# Power_Distribution_24v.net
KiCad netlist of a schematic drawn in EAGLE
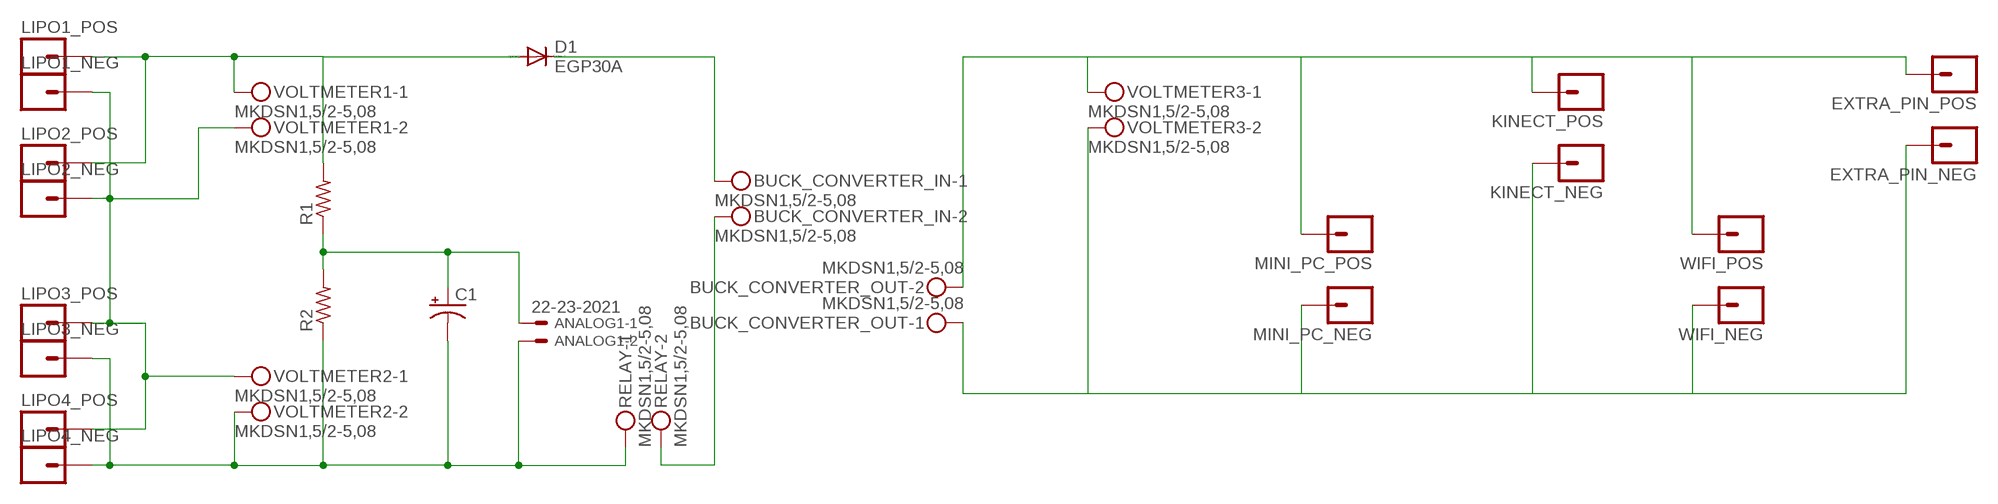
[diagram p0: schematic, sheet 1]

(export (version "E")
  (design (tool "Eeschema 10.0.6"))
  (components
    (comp (ref "ANALOG1")
      (value "22-23-2021")
      (footprint "eagle-import:22-23-2021")
      (fields (field (name "MF") "MOLEX"))
      (libsource (lib "eagle-import") (part "22-23-2021"))
    )
    (comp (ref "BUCK_CONVERTER_IN")
      (value "MKDSN1,5/2-5,08")
      (footprint "eagle-import:MKDSN1,5_2-5,08")
      (libsource (lib "eagle-import") (part "MKDSN1,5/2-5,08"))
    )
    (comp (ref "BUCK_CONVERTER_OUT")
      (value "MKDSN1,5/2-5,08")
      (footprint "eagle-import:MKDSN1,5_2-5,08")
      (libsource (lib "eagle-import") (part "MKDSN1,5/2-5,08"))
    )
    (comp (ref "C1")
      (value "CPOL-USE2-5")
      (footprint "eagle-import:E2-5")
      (libsource (lib "eagle-import") (part "CPOL-USE2-5"))
    )
    (comp (ref "D1")
      (value "EGP30A")
      (footprint "eagle-import:DO201-15")
      (libsource (lib "eagle-import") (part "EGP30A"))
    )
    (comp (ref "EXTRA_PIN_NEG")
      (value "M01PTH_2MM")
      (footprint "eagle-import:1X01_2MM")
      (libsource (lib "eagle-import") (part "M01PTH_2MM"))
    )
    (comp (ref "EXTRA_PIN_POS")
      (value "M01PTH_2MM")
      (footprint "eagle-import:1X01_2MM")
      (libsource (lib "eagle-import") (part "M01PTH_2MM"))
    )
    (comp (ref "KINECT_NEG")
      (value "M01PTH_2MM")
      (footprint "eagle-import:1X01_2MM")
      (libsource (lib "eagle-import") (part "M01PTH_2MM"))
    )
    (comp (ref "KINECT_POS")
      (value "M01PTH_2MM")
      (footprint "eagle-import:1X01_2MM")
      (libsource (lib "eagle-import") (part "M01PTH_2MM"))
    )
    (comp (ref "LIPO1_NEG")
      (value "M01PTH_2MM")
      (footprint "eagle-import:1X01_2MM")
      (libsource (lib "eagle-import") (part "M01PTH_2MM"))
    )
    (comp (ref "LIPO1_POS")
      (value "M01PTH_2MM")
      (footprint "eagle-import:1X01_2MM")
      (libsource (lib "eagle-import") (part "M01PTH_2MM"))
    )
    (comp (ref "LIPO2_NEG")
      (value "M01PTH_2MM")
      (footprint "eagle-import:1X01_2MM")
      (libsource (lib "eagle-import") (part "M01PTH_2MM"))
    )
    (comp (ref "LIPO2_POS")
      (value "M01PTH_2MM")
      (footprint "eagle-import:1X01_2MM")
      (libsource (lib "eagle-import") (part "M01PTH_2MM"))
    )
    (comp (ref "LIPO3_NEG")
      (value "M01PTH_2MM")
      (footprint "eagle-import:1X01_2MM")
      (libsource (lib "eagle-import") (part "M01PTH_2MM"))
    )
    (comp (ref "LIPO3_POS")
      (value "M01PTH_2MM")
      (footprint "eagle-import:1X01_2MM")
      (libsource (lib "eagle-import") (part "M01PTH_2MM"))
    )
    (comp (ref "LIPO4_NEG")
      (value "M01PTH_2MM")
      (footprint "eagle-import:1X01_2MM")
      (libsource (lib "eagle-import") (part "M01PTH_2MM"))
    )
    (comp (ref "LIPO4_POS")
      (value "M01PTH_2MM")
      (footprint "eagle-import:1X01_2MM")
      (libsource (lib "eagle-import") (part "M01PTH_2MM"))
    )
    (comp (ref "MINI_PC_NEG")
      (value "M01PTH_2MM")
      (footprint "eagle-import:1X01_2MM")
      (libsource (lib "eagle-import") (part "M01PTH_2MM"))
    )
    (comp (ref "MINI_PC_POS")
      (value "M01PTH_2MM")
      (footprint "eagle-import:1X01_2MM")
      (libsource (lib "eagle-import") (part "M01PTH_2MM"))
    )
    (comp (ref "R1")
      (value "R-US_0207/10")
      (footprint "eagle-import:0207_10")
      (libsource (lib "eagle-import") (part "R-US_0207/10"))
    )
    (comp (ref "R2")
      (value "R-US_0207/10")
      (footprint "eagle-import:0207_10")
      (libsource (lib "eagle-import") (part "R-US_0207/10"))
    )
    (comp (ref "RELAY")
      (value "MKDSN1,5/2-5,08")
      (footprint "eagle-import:MKDSN1,5_2-5,08")
      (libsource (lib "eagle-import") (part "MKDSN1,5/2-5,08"))
    )
    (comp (ref "VOLTMETER1")
      (value "MKDSN1,5/2-5,08")
      (footprint "eagle-import:MKDSN1,5_2-5,08")
      (libsource (lib "eagle-import") (part "MKDSN1,5/2-5,08"))
    )
    (comp (ref "VOLTMETER2")
      (value "MKDSN1,5/2-5,08")
      (footprint "eagle-import:MKDSN1,5_2-5,08")
      (libsource (lib "eagle-import") (part "MKDSN1,5/2-5,08"))
    )
    (comp (ref "VOLTMETER3")
      (value "MKDSN1,5/2-5,08")
      (footprint "eagle-import:MKDSN1,5_2-5,08")
      (libsource (lib "eagle-import") (part "MKDSN1,5/2-5,08"))
    )
    (comp (ref "WIFI_NEG")
      (value "M01PTH_2MM")
      (footprint "eagle-import:1X01_2MM")
      (libsource (lib "eagle-import") (part "M01PTH_2MM"))
    )
    (comp (ref "WIFI_POS")
      (value "M01PTH_2MM")
      (footprint "eagle-import:1X01_2MM")
      (libsource (lib "eagle-import") (part "M01PTH_2MM"))
    )
  )
  (nets
    (net (code "1") (name "Net-(ANALOG1A-S)") (class "Default")
      (node (ref "ANALOG1") (pin "1") (pinfunction "S_1") (pintype "passive"))
      (node (ref "C1") (pin "+") (pinfunction "+_+") (pintype "passive"))
      (node (ref "R1") (pin "1") (pinfunction "1_1") (pintype "passive"))
      (node (ref "R2") (pin "2") (pinfunction "2_2") (pintype "passive"))
    )
    (net (code "2") (name "Net-(ANALOG1B-S)") (class "Default")
      (node (ref "ANALOG1") (pin "2") (pinfunction "S_2") (pintype "passive"))
      (node (ref "C1") (pin "-") (pinfunction "-_-") (pintype "passive"))
      (node (ref "LIPO3_NEG") (pin "1") (pinfunction "1_1") (pintype "passive"))
      (node (ref "LIPO4_NEG") (pin "1") (pinfunction "1_1") (pintype "passive"))
      (node (ref "R2") (pin "1") (pinfunction "1_1") (pintype "passive"))
      (node (ref "RELAY") (pin "1") (pinfunction "KL_1") (pintype "passive"))
      (node (ref "VOLTMETER2") (pin "2") (pinfunction "KL_2") (pintype "passive"))
    )
    (net (code "3") (name "Net-(BUCK_CONVERTER_INA-KL)") (class "Default")
      (node (ref "BUCK_CONVERTER_IN") (pin "1") (pinfunction "KL_1") (pintype "passive"))
      (node (ref "D1") (pin "C") (pinfunction "C_C") (pintype "passive"))
    )
    (net (code "4") (name "Net-(BUCK_CONVERTER_INB-KL)") (class "Default")
      (node (ref "BUCK_CONVERTER_IN") (pin "2") (pinfunction "KL_2") (pintype "passive"))
      (node (ref "RELAY") (pin "2") (pinfunction "KL_2") (pintype "passive"))
    )
    (net (code "5") (name "Net-(BUCK_CONVERTER_OUTA-KL)") (class "Default")
      (node (ref "BUCK_CONVERTER_OUT") (pin "1") (pinfunction "KL_1") (pintype "passive"))
      (node (ref "EXTRA_PIN_NEG") (pin "1") (pinfunction "1_1") (pintype "passive"))
      (node (ref "KINECT_NEG") (pin "1") (pinfunction "1_1") (pintype "passive"))
      (node (ref "MINI_PC_NEG") (pin "1") (pinfunction "1_1") (pintype "passive"))
      (node (ref "VOLTMETER3") (pin "2") (pinfunction "KL_2") (pintype "passive"))
      (node (ref "WIFI_NEG") (pin "1") (pinfunction "1_1") (pintype "passive"))
    )
    (net (code "6") (name "Net-(BUCK_CONVERTER_OUTB-KL)") (class "Default")
      (node (ref "BUCK_CONVERTER_OUT") (pin "2") (pinfunction "KL_2") (pintype "passive"))
      (node (ref "EXTRA_PIN_POS") (pin "1") (pinfunction "1_1") (pintype "passive"))
      (node (ref "KINECT_POS") (pin "1") (pinfunction "1_1") (pintype "passive"))
      (node (ref "MINI_PC_POS") (pin "1") (pinfunction "1_1") (pintype "passive"))
      (node (ref "VOLTMETER3") (pin "1") (pinfunction "KL_1") (pintype "passive"))
      (node (ref "WIFI_POS") (pin "1") (pinfunction "1_1") (pintype "passive"))
    )
    (net (code "7") (name "Net-(VOLTMETER1A-KL)") (class "Default")
      (node (ref "D1") (pin "A") (pinfunction "A_A") (pintype "passive"))
      (node (ref "LIPO1_POS") (pin "1") (pinfunction "1_1") (pintype "passive"))
      (node (ref "LIPO2_POS") (pin "1") (pinfunction "1_1") (pintype "passive"))
      (node (ref "R1") (pin "2") (pinfunction "2_2") (pintype "passive"))
      (node (ref "VOLTMETER1") (pin "1") (pinfunction "KL_1") (pintype "passive"))
    )
    (net (code "8") (name "Net-(VOLTMETER1B-KL)") (class "Default")
      (node (ref "LIPO1_NEG") (pin "1") (pinfunction "1_1") (pintype "passive"))
      (node (ref "LIPO2_NEG") (pin "1") (pinfunction "1_1") (pintype "passive"))
      (node (ref "LIPO3_POS") (pin "1") (pinfunction "1_1") (pintype "passive"))
      (node (ref "LIPO4_POS") (pin "1") (pinfunction "1_1") (pintype "passive"))
      (node (ref "VOLTMETER1") (pin "2") (pinfunction "KL_2") (pintype "passive"))
      (node (ref "VOLTMETER2") (pin "1") (pinfunction "KL_1") (pintype "passive"))
    )
  )
)
